# ADAPT.net
KiCad netlist of a schematic drawn in EAGLE
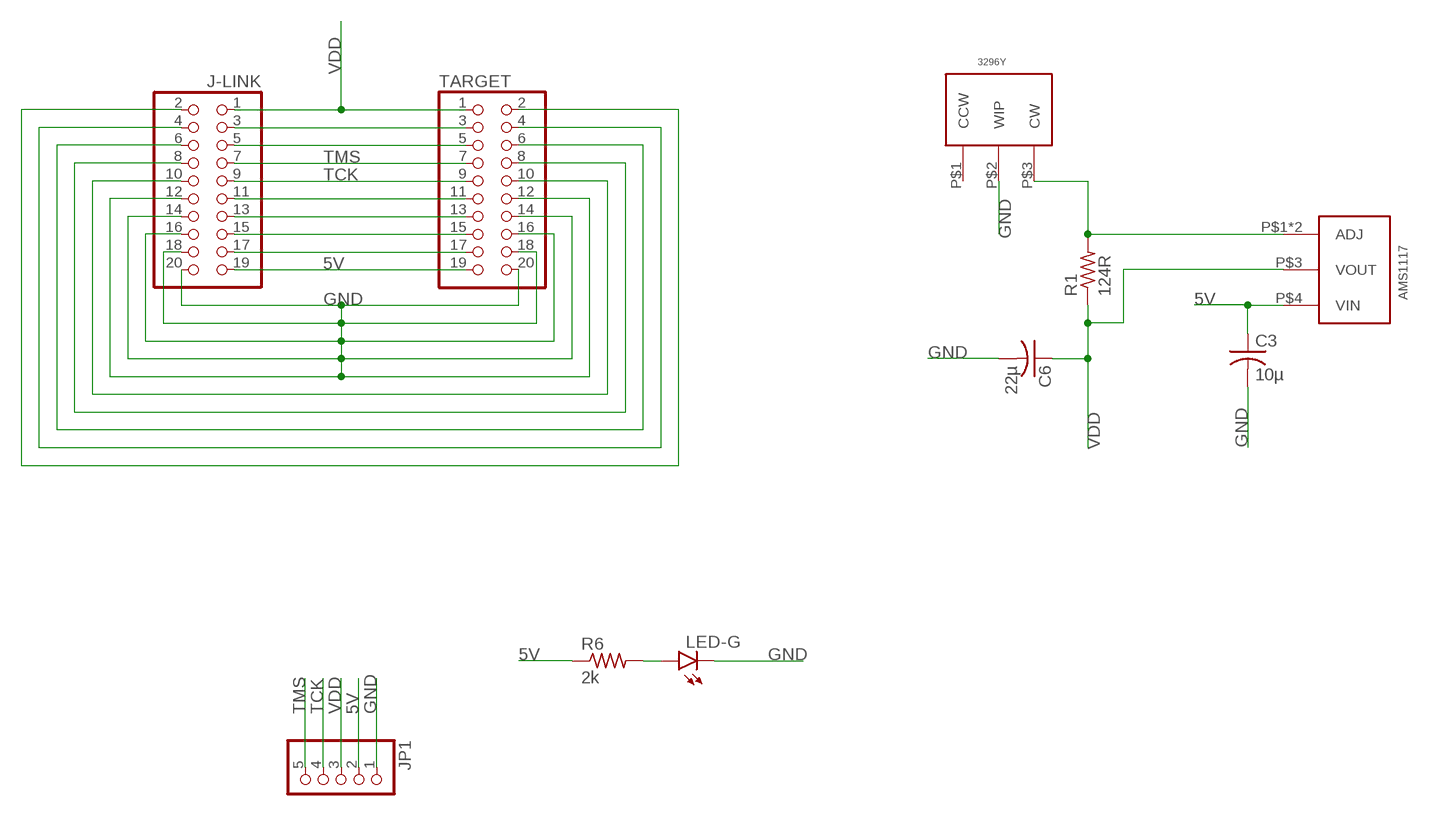
[diagram p0: schematic, sheet 1]

(export (version "E")
  (design (tool "Eeschema 10.0.6"))
  (components
    (comp (ref "3296Y")
      (value "3296Y")
      (footprint "eagle-import:3296Y")
      (libsource (lib "eagle-import") (part "3296Y"))
    )
    (comp (ref "AMS1117")
      (value "AMS1117")
      (footprint "eagle-import:AMS1117")
      (libsource (lib "eagle-import") (part "AMS1117"))
    )
    (comp (ref "C3")
      (value "10µ")
      (footprint "eagle-import:C1206")
      (libsource (lib "eagle-import") (part "C-USC1206"))
    )
    (comp (ref "C6")
      (value "22µ")
      (footprint "eagle-import:C1206")
      (libsource (lib "eagle-import") (part "C-USC1206"))
    )
    (comp (ref "J-LINK")
      (value "PINHD-2X10")
      (footprint "eagle-import:2X10")
      (libsource (lib "eagle-import") (part "PINHD-2X10"))
    )
    (comp (ref "JP1")
      (value "PINHD-1X5")
      (footprint "eagle-import:1X05")
      (libsource (lib "eagle-import") (part "PINHD-1X5"))
    )
    (comp (ref "LED-G")
      (value "LEDCHIPLED_0603")
      (footprint "eagle-import:CHIPLED_0603")
      (libsource (lib "eagle-import") (part "LEDCHIPLED_0603"))
    )
    (comp (ref "R1")
      (value "124R")
      (footprint "eagle-import:R0805")
      (libsource (lib "eagle-import") (part "R-US_R0805"))
    )
    (comp (ref "R6")
      (value "2k")
      (footprint "eagle-import:R0603")
      (libsource (lib "eagle-import") (part "resistor_348_R-US_R0603"))
    )
    (comp (ref "TARGET")
      (value "PINHD-2X10")
      (footprint "eagle-import:2X10")
      (libsource (lib "eagle-import") (part "pinheadCS_PINHD-2X10"))
    )
  )
  (nets
    (net (code "1") (name "/5V") (class "Default")
      (node (ref "AMS1117") (pin "P$4") (pinfunction "VIN_P$4") (pintype "bidirectional"))
      (node (ref "C3") (pin "1") (pinfunction "1_1") (pintype "passive"))
      (node (ref "J-LINK") (pin "19") (pinfunction "19_19") (pintype "passive"))
      (node (ref "JP1") (pin "2") (pinfunction "2_2") (pintype "passive"))
      (node (ref "R6") (pin "1") (pinfunction "1_1") (pintype "passive"))
      (node (ref "TARGET") (pin "19") (pinfunction "19_19") (pintype "passive"))
    )
    (net (code "2") (name "/GND") (class "Default")
      (node (ref "3296Y") (pin "P$2") (pinfunction "WIP_P$2") (pintype "bidirectional"))
      (node (ref "C3") (pin "2") (pinfunction "2_2") (pintype "passive"))
      (node (ref "C6") (pin "2") (pinfunction "2_2") (pintype "passive"))
      (node (ref "J-LINK") (pin "12") (pinfunction "12_12") (pintype "passive"))
      (node (ref "J-LINK") (pin "14") (pinfunction "14_14") (pintype "passive"))
      (node (ref "J-LINK") (pin "16") (pinfunction "16_16") (pintype "passive"))
      (node (ref "J-LINK") (pin "18") (pinfunction "18_18") (pintype "passive"))
      (node (ref "J-LINK") (pin "20") (pinfunction "20_20") (pintype "passive"))
      (node (ref "JP1") (pin "1") (pinfunction "1_1") (pintype "passive"))
      (node (ref "LED-G") (pin "C") (pinfunction "C_C") (pintype "passive"))
      (node (ref "TARGET") (pin "12") (pinfunction "12_12") (pintype "passive"))
      (node (ref "TARGET") (pin "14") (pinfunction "14_14") (pintype "passive"))
      (node (ref "TARGET") (pin "16") (pinfunction "16_16") (pintype "passive"))
      (node (ref "TARGET") (pin "18") (pinfunction "18_18") (pintype "passive"))
      (node (ref "TARGET") (pin "20") (pinfunction "20_20") (pintype "passive"))
    )
    (net (code "3") (name "/TCK") (class "Default")
      (node (ref "J-LINK") (pin "9") (pinfunction "9_9") (pintype "passive"))
      (node (ref "JP1") (pin "4") (pinfunction "4_4") (pintype "passive"))
      (node (ref "TARGET") (pin "9") (pinfunction "9_9") (pintype "passive"))
    )
    (net (code "4") (name "/TMS") (class "Default")
      (node (ref "J-LINK") (pin "7") (pinfunction "7_7") (pintype "passive"))
      (node (ref "JP1") (pin "5") (pinfunction "5_5") (pintype "passive"))
      (node (ref "TARGET") (pin "7") (pinfunction "7_7") (pintype "passive"))
    )
    (net (code "5") (name "/VDD") (class "Default")
      (node (ref "AMS1117") (pin "P$3") (pinfunction "VOUT_P$3") (pintype "bidirectional"))
      (node (ref "C6") (pin "1") (pinfunction "1_1") (pintype "passive"))
      (node (ref "J-LINK") (pin "1") (pinfunction "1_1") (pintype "passive"))
      (node (ref "JP1") (pin "3") (pinfunction "3_3") (pintype "passive"))
      (node (ref "R1") (pin "1") (pinfunction "1_1") (pintype "passive"))
      (node (ref "TARGET") (pin "1") (pinfunction "1_1") (pintype "passive"))
    )
    (net (code "6") (name "Net-(3296Y-CW)") (class "Default")
      (node (ref "3296Y") (pin "P$3") (pinfunction "CW_P$3") (pintype "bidirectional"))
      (node (ref "AMS1117") (pin "P$1") (pinfunction "ADJ_P$1") (pintype "bidirectional"))
      (node (ref "AMS1117") (pin "P$2") (pinfunction "ADJ_P$2") (pintype "bidirectional"))
      (node (ref "R1") (pin "2") (pinfunction "2_2") (pintype "passive"))
    )
    (net (code "7") (name "Net-(J-LINK-Pad2)") (class "Default")
      (node (ref "J-LINK") (pin "2") (pinfunction "2_2") (pintype "passive"))
      (node (ref "TARGET") (pin "2") (pinfunction "2_2") (pintype "passive"))
    )
    (net (code "8") (name "Net-(J-LINK-Pad3)") (class "Default")
      (node (ref "J-LINK") (pin "3") (pinfunction "3_3") (pintype "passive"))
      (node (ref "TARGET") (pin "3") (pinfunction "3_3") (pintype "passive"))
    )
    (net (code "9") (name "Net-(J-LINK-Pad4)") (class "Default")
      (node (ref "J-LINK") (pin "4") (pinfunction "4_4") (pintype "passive"))
      (node (ref "TARGET") (pin "4") (pinfunction "4_4") (pintype "passive"))
    )
    (net (code "10") (name "Net-(J-LINK-Pad5)") (class "Default")
      (node (ref "J-LINK") (pin "5") (pinfunction "5_5") (pintype "passive"))
      (node (ref "TARGET") (pin "5") (pinfunction "5_5") (pintype "passive"))
    )
    (net (code "11") (name "Net-(J-LINK-Pad6)") (class "Default")
      (node (ref "J-LINK") (pin "6") (pinfunction "6_6") (pintype "passive"))
      (node (ref "TARGET") (pin "6") (pinfunction "6_6") (pintype "passive"))
    )
    (net (code "12") (name "Net-(J-LINK-Pad8)") (class "Default")
      (node (ref "J-LINK") (pin "8") (pinfunction "8_8") (pintype "passive"))
      (node (ref "TARGET") (pin "8") (pinfunction "8_8") (pintype "passive"))
    )
    (net (code "13") (name "Net-(J-LINK-Pad10)") (class "Default")
      (node (ref "J-LINK") (pin "10") (pinfunction "10_10") (pintype "passive"))
      (node (ref "TARGET") (pin "10") (pinfunction "10_10") (pintype "passive"))
    )
    (net (code "14") (name "Net-(J-LINK-Pad11)") (class "Default")
      (node (ref "J-LINK") (pin "11") (pinfunction "11_11") (pintype "passive"))
      (node (ref "TARGET") (pin "11") (pinfunction "11_11") (pintype "passive"))
    )
    (net (code "15") (name "Net-(J-LINK-Pad13)") (class "Default")
      (node (ref "J-LINK") (pin "13") (pinfunction "13_13") (pintype "passive"))
      (node (ref "TARGET") (pin "13") (pinfunction "13_13") (pintype "passive"))
    )
    (net (code "16") (name "Net-(J-LINK-Pad15)") (class "Default")
      (node (ref "J-LINK") (pin "15") (pinfunction "15_15") (pintype "passive"))
      (node (ref "TARGET") (pin "15") (pinfunction "15_15") (pintype "passive"))
    )
    (net (code "17") (name "Net-(J-LINK-Pad17)") (class "Default")
      (node (ref "J-LINK") (pin "17") (pinfunction "17_17") (pintype "passive"))
      (node (ref "TARGET") (pin "17") (pinfunction "17_17") (pintype "passive"))
    )
    (net (code "18") (name "Net-(LED-G-PadA)") (class "Default")
      (node (ref "LED-G") (pin "A") (pinfunction "A_A") (pintype "passive"))
      (node (ref "R6") (pin "2") (pinfunction "2_2") (pintype "passive"))
    )
    (net (code "19") (name "unconnected-(3296Y-CCW-PadP$1)") (class "Default")
      (node (ref "3296Y") (pin "P$1") (pinfunction "CCW_P$1") (pintype "bidirectional"))
    )
  )
)
